# SCH_Project_BalanceCar_2024-01-19.net
KiCad netlist of a schematic drawn in EasyEDA
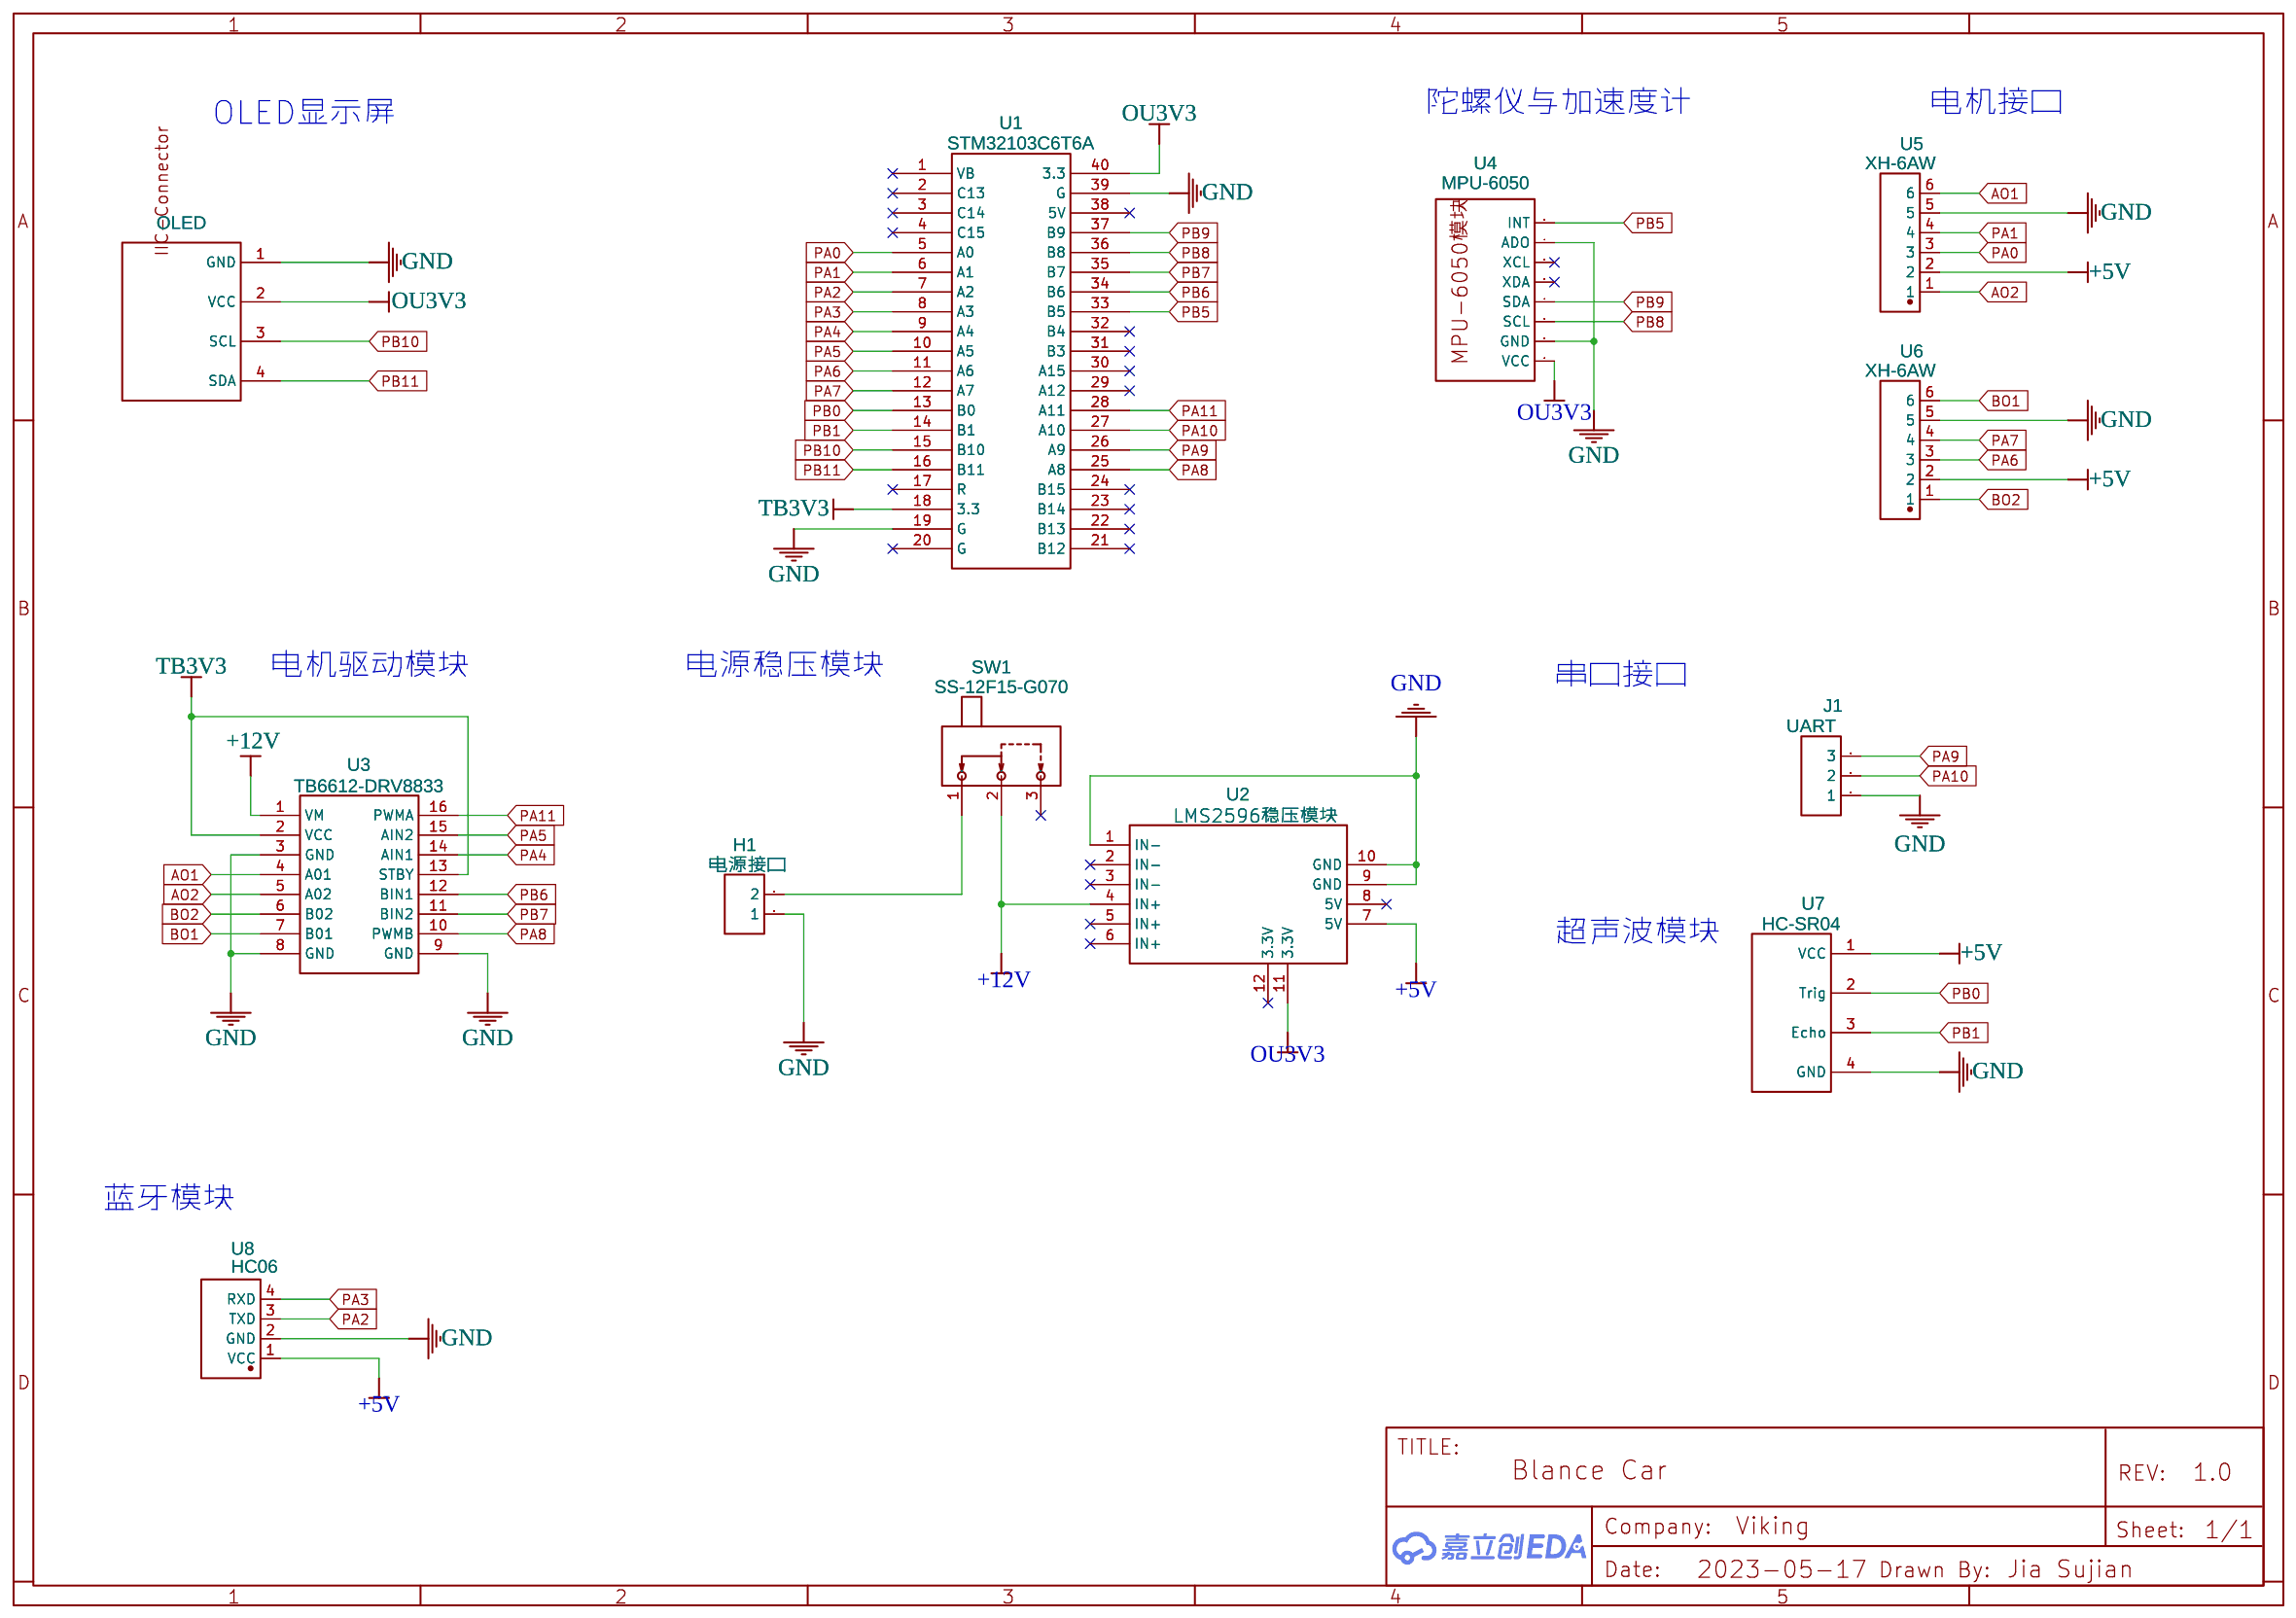
[diagram p0: schematic sheet]

(export (version "E")
  (design (tool "Eeschema 10.0.6"))
  (components
    (comp (ref "H1")
      (value "电源接口")
      (fields (field (name "BOM_Supplier Part") "C49661"))
      (libsource (lib "") (part "HDR-F-2.54_1x2"))
    )
    (comp (ref "J1")
      (value "UART")
      (fields (field (name "BOM_Supplier Part") "C180248"))
      (libsource (lib "") (part "HDR-M-2.54_1x3"))
    )
    (comp (ref "OLED")
      (value "0.96OLED_4P_MODULE_JX")
      (fields (field (name "BOM_Supplier Part") "C9900004566"))
      (libsource (lib "") (part "0.96OLED_4P_MODULE_JX"))
    )
    (comp (ref "SW1")
      (value "SS-12F15-G070")
      (fields (field (name "BOM_Supplier Part") "C2876018"))
      (libsource (lib "") (part "SS-12F15-G070"))
    )
    (comp (ref "U1") (value "STM32103C6T6A") (libsource (lib "") (part "STM32103C6T6A")))
    (comp (ref "U2") (value "LMS2596稳压模块") (libsource (lib "") (part "LMS2596稳压模块")))
    (comp (ref "U3") (value "TB6612-DRV8833") (libsource (lib "") (part "TB6612-DRV8833")))
    (comp (ref "U4") (value "MPU-6050") (libsource (lib "") (part "MPU-6050 六轴模块")))
    (comp (ref "U5")
      (value "XH-6AW")
      (fields (field (name "BOM_Supplier Part") "C3010043"))
      (libsource (lib "") (part "XH-6AW_C3010043"))
    )
    (comp (ref "U6")
      (value "XH-6AW")
      (fields (field (name "BOM_Supplier Part") "C3010043"))
      (libsource (lib "") (part "XH-6AW_C3010043"))
    )
    (comp (ref "U7") (value "HC-SR04") (libsource (lib "") (part "HC-SR04_超声波模块")))
    (comp (ref "U8") (value "HC06") (libsource (lib "") (part "HC06")))
  )
  (nets
    (net (code "1") (name "+5V") (class "Default")
      (node (ref "U2") (pin "7") (pinfunction "5V_7") (pintype "unspecified"))
      (node (ref "U5") (pin "2") (pinfunction "2_2") (pintype "unspecified"))
      (node (ref "U6") (pin "2") (pinfunction "2_2") (pintype "unspecified"))
      (node (ref "U7") (pin "1") (pinfunction "VCC_1") (pintype "unspecified"))
      (node (ref "U8") (pin "1") (pinfunction "VCC_1") (pintype "unspecified"))
    )
    (net (code "2") (name "+12V") (class "Default")
      (node (ref "SW1") (pin "2") (pinfunction "2_2") (pintype "unspecified"))
      (node (ref "U2") (pin "4") (pinfunction "IN+_4") (pintype "unspecified"))
      (node (ref "U3") (pin "1") (pinfunction "VM_1") (pintype "unspecified"))
    )
    (net (code "3") (name "AO1") (class "Default")
      (node (ref "U3") (pin "4") (pinfunction "A01_4") (pintype "unspecified"))
      (node (ref "U5") (pin "6") (pinfunction "6_6") (pintype "unspecified"))
    )
    (net (code "4") (name "AO2") (class "Default")
      (node (ref "U3") (pin "5") (pinfunction "A02_5") (pintype "unspecified"))
      (node (ref "U5") (pin "1") (pinfunction "1_1") (pintype "unspecified"))
    )
    (net (code "5") (name "BO1") (class "Default")
      (node (ref "U3") (pin "7") (pinfunction "B01_7") (pintype "unspecified"))
      (node (ref "U6") (pin "6") (pinfunction "6_6") (pintype "unspecified"))
    )
    (net (code "6") (name "BO2") (class "Default")
      (node (ref "U3") (pin "6") (pinfunction "B02_6") (pintype "unspecified"))
      (node (ref "U6") (pin "1") (pinfunction "1_1") (pintype "unspecified"))
    )
    (net (code "7") (name "GND") (class "Default")
      (node (ref "H1") (pin "1") (pinfunction "1_1") (pintype "input"))
      (node (ref "J1") (pin "1") (pinfunction "1_1") (pintype "input"))
      (node (ref "OLED") (pin "1") (pinfunction "GND_1") (pintype "unspecified"))
      (node (ref "U1") (pin "19") (pinfunction "G_19") (pintype "unspecified"))
      (node (ref "U1") (pin "39") (pinfunction "G_39") (pintype "unspecified"))
      (node (ref "U2") (pin "1") (pinfunction "IN-_1") (pintype "unspecified"))
      (node (ref "U2") (pin "10") (pinfunction "GND_10") (pintype "unspecified"))
      (node (ref "U2") (pin "9") (pinfunction "GND_9") (pintype "unspecified"))
      (node (ref "U3") (pin "3") (pinfunction "GND_3") (pintype "unspecified"))
      (node (ref "U3") (pin "8") (pinfunction "GND_8") (pintype "unspecified"))
      (node (ref "U3") (pin "9") (pinfunction "GND_9") (pintype "unspecified"))
      (node (ref "U4") (pin "2") (pinfunction "GND_2") (pintype "unspecified"))
      (node (ref "U4") (pin "7") (pinfunction "ADO_7") (pintype "unspecified"))
      (node (ref "U5") (pin "5") (pinfunction "5_5") (pintype "unspecified"))
      (node (ref "U6") (pin "5") (pinfunction "5_5") (pintype "unspecified"))
      (node (ref "U7") (pin "4") (pinfunction "GND_4") (pintype "unspecified"))
      (node (ref "U8") (pin "2") (pinfunction "GND_2") (pintype "unspecified"))
    )
    (net (code "8") (name "Net-(H1-Pad2)") (class "Default")
      (node (ref "H1") (pin "2") (pinfunction "2_2") (pintype "input"))
      (node (ref "SW1") (pin "1") (pinfunction "1_1") (pintype "unspecified"))
    )
    (net (code "9") (name "OU3V3") (class "Default")
      (node (ref "OLED") (pin "2") (pinfunction "VCC_2") (pintype "unspecified"))
      (node (ref "U1") (pin "40") (pinfunction "3.3_40") (pintype "unspecified"))
      (node (ref "U2") (pin "11") (pinfunction "3.3V_11") (pintype "unspecified"))
      (node (ref "U4") (pin "1") (pinfunction "VCC_1") (pintype "unspecified"))
    )
    (net (code "10") (name "PA0") (class "Default")
      (node (ref "U1") (pin "5") (pinfunction "A0_5") (pintype "unspecified"))
      (node (ref "U5") (pin "3") (pinfunction "3_3") (pintype "unspecified"))
    )
    (net (code "11") (name "PA1") (class "Default")
      (node (ref "U1") (pin "6") (pinfunction "A1_6") (pintype "unspecified"))
      (node (ref "U5") (pin "4") (pinfunction "4_4") (pintype "unspecified"))
    )
    (net (code "12") (name "PA2") (class "Default")
      (node (ref "U1") (pin "7") (pinfunction "A2_7") (pintype "unspecified"))
      (node (ref "U8") (pin "3") (pinfunction "TXD_3") (pintype "unspecified"))
    )
    (net (code "13") (name "PA3") (class "Default")
      (node (ref "U1") (pin "8") (pinfunction "A3_8") (pintype "unspecified"))
      (node (ref "U8") (pin "4") (pinfunction "RXD_4") (pintype "unspecified"))
    )
    (net (code "14") (name "PA4") (class "Default")
      (node (ref "U1") (pin "9") (pinfunction "A4_9") (pintype "unspecified"))
      (node (ref "U3") (pin "14") (pinfunction "AIN1_14") (pintype "unspecified"))
    )
    (net (code "15") (name "PA5") (class "Default")
      (node (ref "U1") (pin "10") (pinfunction "A5_10") (pintype "unspecified"))
      (node (ref "U3") (pin "15") (pinfunction "AIN2_15") (pintype "unspecified"))
    )
    (net (code "16") (name "PA6") (class "Default")
      (node (ref "U1") (pin "11") (pinfunction "A6_11") (pintype "unspecified"))
      (node (ref "U6") (pin "3") (pinfunction "3_3") (pintype "unspecified"))
    )
    (net (code "17") (name "PA7") (class "Default")
      (node (ref "U1") (pin "12") (pinfunction "A7_12") (pintype "unspecified"))
      (node (ref "U6") (pin "4") (pinfunction "4_4") (pintype "unspecified"))
    )
    (net (code "18") (name "PA8") (class "Default")
      (node (ref "U1") (pin "25") (pinfunction "A8_25") (pintype "unspecified"))
      (node (ref "U3") (pin "10") (pinfunction "PWMB_10") (pintype "unspecified"))
    )
    (net (code "19") (name "PA9") (class "Default")
      (node (ref "J1") (pin "3") (pinfunction "3_3") (pintype "input"))
      (node (ref "U1") (pin "26") (pinfunction "A9_26") (pintype "unspecified"))
    )
    (net (code "20") (name "PA10") (class "Default")
      (node (ref "J1") (pin "2") (pinfunction "2_2") (pintype "input"))
      (node (ref "U1") (pin "27") (pinfunction "A10_27") (pintype "unspecified"))
    )
    (net (code "21") (name "PA11") (class "Default")
      (node (ref "U1") (pin "28") (pinfunction "A11_28") (pintype "unspecified"))
      (node (ref "U3") (pin "16") (pinfunction "PWMA_16") (pintype "unspecified"))
    )
    (net (code "22") (name "PB0") (class "Default")
      (node (ref "U1") (pin "13") (pinfunction "B0_13") (pintype "unspecified"))
      (node (ref "U7") (pin "2") (pinfunction "Trig_2") (pintype "unspecified"))
    )
    (net (code "23") (name "PB1") (class "Default")
      (node (ref "U1") (pin "14") (pinfunction "B1_14") (pintype "unspecified"))
      (node (ref "U7") (pin "3") (pinfunction "Echo_3") (pintype "unspecified"))
    )
    (net (code "24") (name "PB5") (class "Default")
      (node (ref "U1") (pin "33") (pinfunction "B5_33") (pintype "unspecified"))
      (node (ref "U4") (pin "8") (pinfunction "INT_8") (pintype "unspecified"))
    )
    (net (code "25") (name "PB6") (class "Default")
      (node (ref "U1") (pin "34") (pinfunction "B6_34") (pintype "unspecified"))
      (node (ref "U3") (pin "12") (pinfunction "BIN1_12") (pintype "unspecified"))
    )
    (net (code "26") (name "PB7") (class "Default")
      (node (ref "U1") (pin "35") (pinfunction "B7_35") (pintype "unspecified"))
      (node (ref "U3") (pin "11") (pinfunction "BIN2_11") (pintype "unspecified"))
    )
    (net (code "27") (name "PB8") (class "Default")
      (node (ref "U1") (pin "36") (pinfunction "B8_36") (pintype "unspecified"))
      (node (ref "U4") (pin "3") (pinfunction "SCL_3") (pintype "unspecified"))
    )
    (net (code "28") (name "PB9") (class "Default")
      (node (ref "U1") (pin "37") (pinfunction "B9_37") (pintype "unspecified"))
      (node (ref "U4") (pin "4") (pinfunction "SDA_4") (pintype "unspecified"))
    )
    (net (code "29") (name "PB10") (class "Default")
      (node (ref "OLED") (pin "3") (pinfunction "SCL_3") (pintype "unspecified"))
      (node (ref "U1") (pin "15") (pinfunction "B10_15") (pintype "unspecified"))
    )
    (net (code "30") (name "PB11") (class "Default")
      (node (ref "OLED") (pin "4") (pinfunction "SDA_4") (pintype "unspecified"))
      (node (ref "U1") (pin "16") (pinfunction "B11_16") (pintype "unspecified"))
    )
    (net (code "31") (name "TB3V3") (class "Default")
      (node (ref "U1") (pin "18") (pinfunction "3.3_18") (pintype "unspecified"))
      (node (ref "U3") (pin "13") (pinfunction "STBY_13") (pintype "unspecified"))
      (node (ref "U3") (pin "2") (pinfunction "VCC_2") (pintype "unspecified"))
    )
    (net (code "32") (name "unconnected-(SW1-Pad3)") (class "Default")
      (node (ref "SW1") (pin "3") (pinfunction "3_3") (pintype "unspecified+no_connect"))
    )
    (net (code "33") (name "unconnected-(U1-5V-Pad38)") (class "Default")
      (node (ref "U1") (pin "38") (pinfunction "5V_38") (pintype "unspecified+no_connect"))
    )
    (net (code "34") (name "unconnected-(U1-A12-Pad29)") (class "Default")
      (node (ref "U1") (pin "29") (pinfunction "A12_29") (pintype "unspecified+no_connect"))
    )
    (net (code "35") (name "unconnected-(U1-A15-Pad30)") (class "Default")
      (node (ref "U1") (pin "30") (pinfunction "A15_30") (pintype "unspecified+no_connect"))
    )
    (net (code "36") (name "unconnected-(U1-B3-Pad31)") (class "Default")
      (node (ref "U1") (pin "31") (pinfunction "B3_31") (pintype "unspecified+no_connect"))
    )
    (net (code "37") (name "unconnected-(U1-B4-Pad32)") (class "Default")
      (node (ref "U1") (pin "32") (pinfunction "B4_32") (pintype "unspecified+no_connect"))
    )
    (net (code "38") (name "unconnected-(U1-B12-Pad21)") (class "Default")
      (node (ref "U1") (pin "21") (pinfunction "B12_21") (pintype "unspecified+no_connect"))
    )
    (net (code "39") (name "unconnected-(U1-B13-Pad22)") (class "Default")
      (node (ref "U1") (pin "22") (pinfunction "B13_22") (pintype "unspecified+no_connect"))
    )
    (net (code "40") (name "unconnected-(U1-B14-Pad23)") (class "Default")
      (node (ref "U1") (pin "23") (pinfunction "B14_23") (pintype "unspecified+no_connect"))
    )
    (net (code "41") (name "unconnected-(U1-B15-Pad24)") (class "Default")
      (node (ref "U1") (pin "24") (pinfunction "B15_24") (pintype "unspecified+no_connect"))
    )
    (net (code "42") (name "unconnected-(U1-C13-Pad2)") (class "Default")
      (node (ref "U1") (pin "2") (pinfunction "C13_2") (pintype "unspecified+no_connect"))
    )
    (net (code "43") (name "unconnected-(U1-C14-Pad3)") (class "Default")
      (node (ref "U1") (pin "3") (pinfunction "C14_3") (pintype "unspecified+no_connect"))
    )
    (net (code "44") (name "unconnected-(U1-C15-Pad4)") (class "Default")
      (node (ref "U1") (pin "4") (pinfunction "C15_4") (pintype "unspecified+no_connect"))
    )
    (net (code "45") (name "unconnected-(U1-G-Pad20)") (class "Default")
      (node (ref "U1") (pin "20") (pinfunction "G_20") (pintype "unspecified+no_connect"))
    )
    (net (code "46") (name "unconnected-(U1-R-Pad17)") (class "Default")
      (node (ref "U1") (pin "17") (pinfunction "R_17") (pintype "unspecified+no_connect"))
    )
    (net (code "47") (name "unconnected-(U1-VB-Pad1)") (class "Default")
      (node (ref "U1") (pin "1") (pinfunction "VB_1") (pintype "unspecified+no_connect"))
    )
    (net (code "48") (name "unconnected-(U2-3.3V-Pad12)") (class "Default")
      (node (ref "U2") (pin "12") (pinfunction "3.3V_12") (pintype "unspecified+no_connect"))
    )
    (net (code "49") (name "unconnected-(U2-5V-Pad8)") (class "Default")
      (node (ref "U2") (pin "8") (pinfunction "5V_8") (pintype "unspecified+no_connect"))
    )
    (net (code "50") (name "unconnected-(U2-IN+-Pad5)") (class "Default")
      (node (ref "U2") (pin "5") (pinfunction "IN+_5") (pintype "unspecified+no_connect"))
    )
    (net (code "51") (name "unconnected-(U2-IN+-Pad6)") (class "Default")
      (node (ref "U2") (pin "6") (pinfunction "IN+_6") (pintype "unspecified+no_connect"))
    )
    (net (code "52") (name "unconnected-(U2-IN--Pad2)") (class "Default")
      (node (ref "U2") (pin "2") (pinfunction "IN-_2") (pintype "unspecified+no_connect"))
    )
    (net (code "53") (name "unconnected-(U2-IN--Pad3)") (class "Default")
      (node (ref "U2") (pin "3") (pinfunction "IN-_3") (pintype "unspecified+no_connect"))
    )
    (net (code "54") (name "unconnected-(U4-XCL-Pad6)") (class "Default")
      (node (ref "U4") (pin "6") (pinfunction "XCL_6") (pintype "unspecified+no_connect"))
    )
    (net (code "55") (name "unconnected-(U4-XDA-Pad5)") (class "Default")
      (node (ref "U4") (pin "5") (pinfunction "XDA_5") (pintype "unspecified+no_connect"))
    )
  )
)
